# Transceiver.net
KiCad netlist of a schematic drawn in Altium Designer
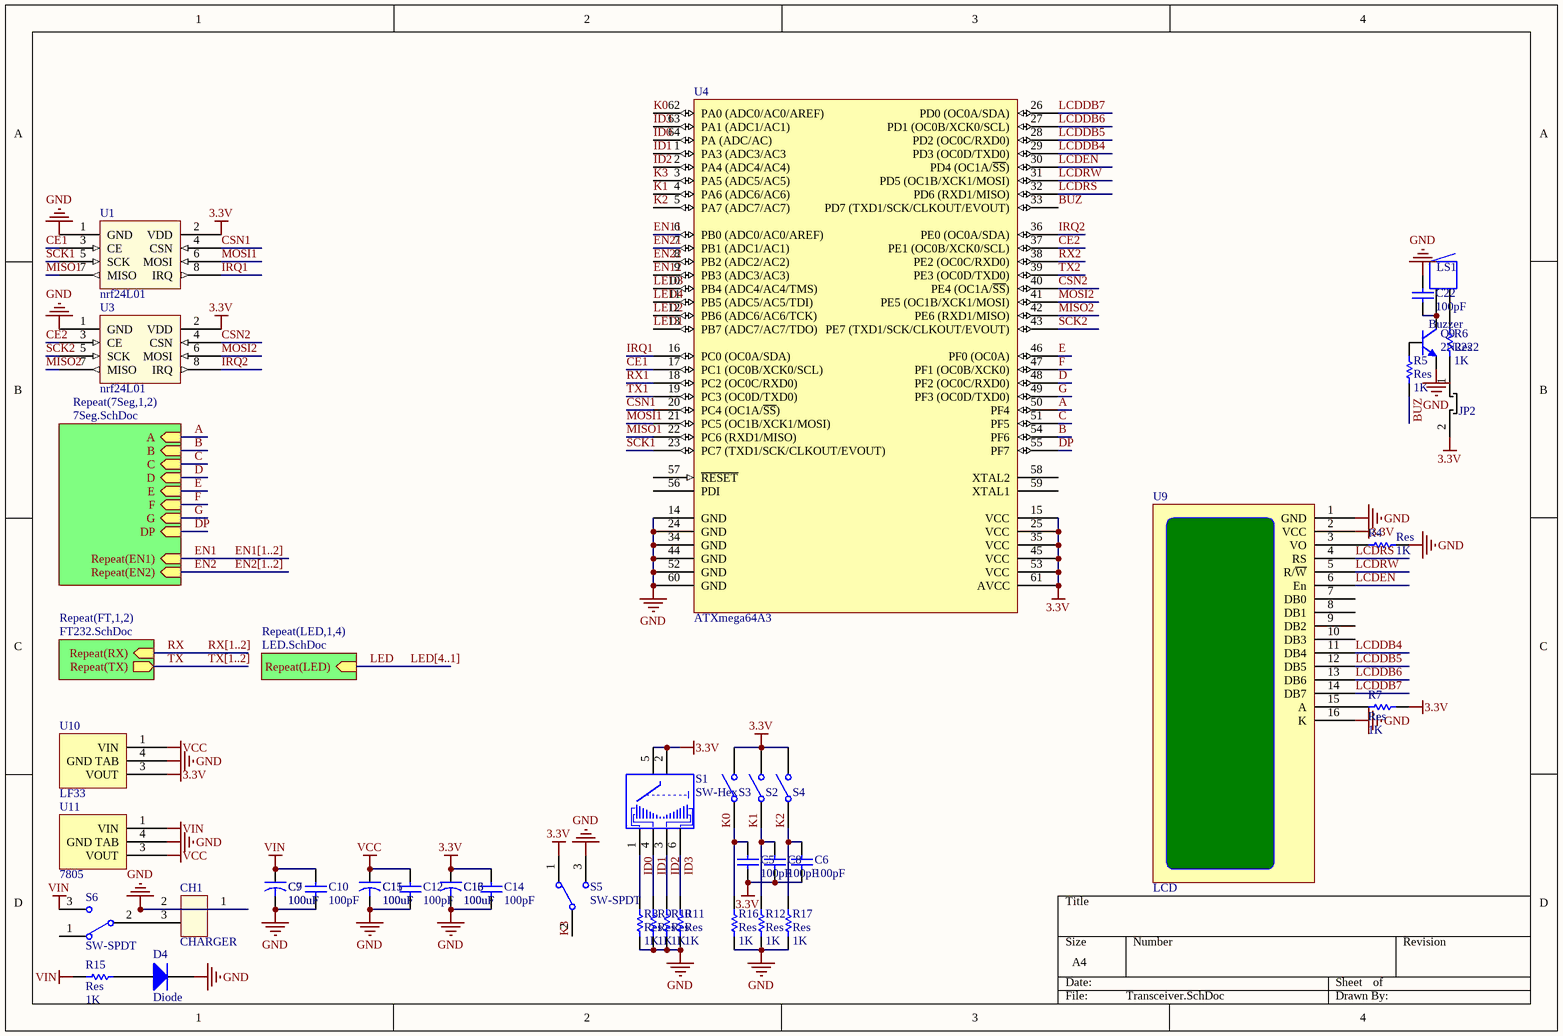
[diagram p0: Transceiver.SchDoc]

(export (version "E")
  (design (tool "Eeschema 10.0.6"))
  (components
    (comp (ref "C5")
      (value "100pF")
      (footprint "2012[0805]")
      (description "Capacitor")
      (fields (field (name "Comment") "Cap_UP") (field (name "PUBLISHER") "Altium Limited"))
      (libsource (lib "KN2CLib") (part "Cap_UP"))
    )
    (comp (ref "C6")
      (value "100pF")
      (footprint "2012[0805]")
      (description "Capacitor")
      (fields (field (name "Comment") "Cap_UP") (field (name "PUBLISHER") "Altium Limited"))
      (libsource (lib "KN2CLib") (part "Cap_UP"))
    )
    (comp (ref "C7")
      (value "100uF")
      (footprint "EL_M")
      (description "Capacitor")
      (fields (field (name "Comment") "Cap_El") (field (name "PUBLISHER") "Altium Limited"))
      (libsource (lib "KN2CLib") (part "Cap_El"))
    )
    (comp (ref "C8")
      (value "100pF")
      (footprint "2012[0805]")
      (description "Capacitor")
      (fields (field (name "Comment") "Cap_UP") (field (name "PUBLISHER") "Altium Limited"))
      (libsource (lib "KN2CLib") (part "Cap_UP"))
    )
    (comp (ref "C9")
      (value "100uF")
      (footprint "EL_M")
      (description "Capacitor")
      (fields (field (name "Comment") "Cap_El") (field (name "PUBLISHER") "Altium Limited"))
      (libsource (lib "KN2CLib") (part "Cap_El"))
    )
    (comp (ref "C10")
      (value "100pF")
      (footprint "2012[0805]")
      (description "Capacitor")
      (fields (field (name "Comment") "Cap_UP") (field (name "PUBLISHER") "Altium Limited"))
      (libsource (lib "KN2CLib") (part "Cap_UP"))
    )
    (comp (ref "C11")
      (value "100uF")
      (footprint "EL_M")
      (description "Capacitor")
      (fields (field (name "Comment") "Cap_El") (field (name "PUBLISHER") "Altium Limited"))
      (libsource (lib "KN2CLib") (part "Cap_El"))
    )
    (comp (ref "C12")
      (value "100pF")
      (footprint "2012[0805]")
      (description "Capacitor")
      (fields (field (name "Comment") "Cap_UP") (field (name "PUBLISHER") "Altium Limited"))
      (libsource (lib "KN2CLib") (part "Cap_UP"))
    )
    (comp (ref "C13")
      (value "100uF")
      (footprint "EL_M")
      (description "Capacitor")
      (fields (field (name "Comment") "Cap_El") (field (name "PUBLISHER") "Altium Limited"))
      (libsource (lib "KN2CLib") (part "Cap_El"))
    )
    (comp (ref "C14")
      (value "100pF")
      (footprint "2012[0805]")
      (description "Capacitor")
      (fields (field (name "Comment") "Cap_UP") (field (name "PUBLISHER") "Altium Limited"))
      (libsource (lib "KN2CLib") (part "Cap_UP"))
    )
    (comp (ref "C15")
      (value "100uF")
      (footprint "EL_M")
      (description "Capacitor")
      (fields (field (name "Comment") "Cap_El") (field (name "PUBLISHER") "Altium Limited"))
      (libsource (lib "KN2CLib") (part "Cap_El"))
    )
    (comp (ref "C16")
      (value "100uF")
      (footprint "EL_M")
      (description "Capacitor")
      (fields (field (name "Comment") "Cap_El") (field (name "PUBLISHER") "Altium Limited"))
      (libsource (lib "KN2CLib") (part "Cap_El"))
    )
    (comp (ref "C22")
      (value "100pF")
      (footprint "2012[0805]")
      (description "Capacitor")
      (fields (field (name "Comment") "Cap_UP") (field (name "PUBLISHER") "Altium Limited"))
      (libsource (lib "KN2CLib") (part "Cap_UP"))
    )
    (comp (ref "CH1") (value "CHARGER") (footprint "CHARGER") (libsource (lib "KN2CLib") (part "CHARGER")))
    (comp (ref "D4")
      (value "Diode")
      (footprint "2012[0805]")
      (description "1 Amp General Purpose Rectifier")
      (fields (field (name "PUBLISHER") "Altium Limited"))
      (libsource (lib "KN2CLib") (part "Diode"))
    )
    (comp (ref "JP2") (value "JUMPER") (footprint "HDR1X2") (libsource (lib "KN2CLib") (part "JUMPER")))
    (comp (ref "LS1")
      (value "Buzzer")
      (footprint "BUZZER")
      (description "Magnetic Transducer Buzzer")
      (fields (field (name "PUBLISHER") "Altium Limited"))
      (libsource (lib "KN2CLib") (part "Buzzer"))
    )
    (comp (ref "Q9")
      (value "2N2222")
      (footprint "SOT-23")
      (description "NPN Bipolar Transistor")
      (fields (field (name "PUBLISHER") "Altium Limited"))
      (libsource (lib "KN2CLib") (part "2N2222"))
    )
    (comp (ref "R4")
      (value "Res")
      (footprint "2012[0805]")
      (description "Semiconductor Resistor")
      (fields (field (name "ALTIUM_VALUE") "1K") (field (name "PUBLISHER") "Altium Limited"))
      (libsource (lib "KN2CLib") (part "Res"))
    )
    (comp (ref "R5")
      (value "Res")
      (footprint "2012[0805]")
      (description "Semiconductor Resistor")
      (fields (field (name "ALTIUM_VALUE") "1K") (field (name "PUBLISHER") "Altium Limited"))
      (libsource (lib "KN2CLib") (part "Res"))
    )
    (comp (ref "R6")
      (value "Res")
      (footprint "2012[0805]")
      (description "Semiconductor Resistor")
      (fields (field (name "ALTIUM_VALUE") "1K") (field (name "PUBLISHER") "Altium Limited"))
      (libsource (lib "KN2CLib") (part "Res"))
    )
    (comp (ref "R7")
      (value "Res")
      (footprint "2012[0805]")
      (description "Semiconductor Resistor")
      (fields (field (name "ALTIUM_VALUE") "1K") (field (name "PUBLISHER") "Altium Limited"))
      (libsource (lib "KN2CLib") (part "Res"))
    )
    (comp (ref "R8")
      (value "Res")
      (footprint "2012[0805]")
      (description "Semiconductor Resistor")
      (fields (field (name "ALTIUM_VALUE") "1K") (field (name "PUBLISHER") "Altium Limited"))
      (libsource (lib "KN2CLib") (part "Res"))
    )
    (comp (ref "R9")
      (value "Res")
      (footprint "2012[0805]")
      (description "Semiconductor Resistor")
      (fields (field (name "ALTIUM_VALUE") "1K") (field (name "PUBLISHER") "Altium Limited"))
      (libsource (lib "KN2CLib") (part "Res"))
    )
    (comp (ref "R10")
      (value "Res")
      (footprint "2012[0805]")
      (description "Semiconductor Resistor")
      (fields (field (name "ALTIUM_VALUE") "1K") (field (name "PUBLISHER") "Altium Limited"))
      (libsource (lib "KN2CLib") (part "Res"))
    )
    (comp (ref "R11")
      (value "Res")
      (footprint "2012[0805]")
      (description "Semiconductor Resistor")
      (fields (field (name "ALTIUM_VALUE") "1K") (field (name "PUBLISHER") "Altium Limited"))
      (libsource (lib "KN2CLib") (part "Res"))
    )
    (comp (ref "R12")
      (value "Res")
      (footprint "2012[0805]")
      (description "Semiconductor Resistor")
      (fields (field (name "ALTIUM_VALUE") "1K") (field (name "PUBLISHER") "Altium Limited"))
      (libsource (lib "KN2CLib") (part "Res"))
    )
    (comp (ref "R15")
      (value "Res")
      (footprint "2012[0805]")
      (description "Semiconductor Resistor")
      (fields (field (name "ALTIUM_VALUE") "1K") (field (name "PUBLISHER") "Altium Limited"))
      (libsource (lib "KN2CLib") (part "Res"))
    )
    (comp (ref "R16")
      (value "Res")
      (footprint "2012[0805]")
      (description "Semiconductor Resistor")
      (fields (field (name "ALTIUM_VALUE") "1K") (field (name "PUBLISHER") "Altium Limited"))
      (libsource (lib "KN2CLib") (part "Res"))
    )
    (comp (ref "R17")
      (value "Res")
      (footprint "2012[0805]")
      (description "Semiconductor Resistor")
      (fields (field (name "ALTIUM_VALUE") "1K") (field (name "PUBLISHER") "Altium Limited"))
      (libsource (lib "KN2CLib") (part "Res"))
    )
    (comp (ref "S1")
      (value "SW-Hex")
      (footprint "SW-HEX")
      (fields (field (name "PUBLISHER") "Altium Limited"))
      (libsource (lib "KN2CLib") (part "SW-Hex"))
    )
    (comp (ref "S2")
      (value "SW-SPST")
      (footprint "PUSH-BUT-SMD")
      (description "Single-Pole, Single-Throw Switch")
      (fields (field (name "PUBLISHER") "Altium Limited"))
      (libsource (lib "KN2CLib") (part "SW-SPST"))
    )
    (comp (ref "S3")
      (value "SW-SPST")
      (footprint "PUSH-BUT")
      (description "Single-Pole, Single-Throw Switch")
      (fields (field (name "PUBLISHER") "Altium Limited"))
      (libsource (lib "KN2CLib") (part "SW-SPST"))
    )
    (comp (ref "S4")
      (value "SW-SPST")
      (footprint "PUSH-BUT")
      (description "Single-Pole, Single-Throw Switch")
      (fields (field (name "PUBLISHER") "Altium Limited"))
      (libsource (lib "KN2CLib") (part "SW-SPST"))
    )
    (comp (ref "S5")
      (value "SW-SPDT")
      (footprint "SW-SPDT")
      (description "SPDT Subminiature Toggle Switch, Right Angle Mounting, Vertical Actuation")
      (fields (field (name "PUBLISHER") "Altium Limited"))
      (libsource (lib "KN2CLib") (part "SW-SPDT"))
    )
    (comp (ref "S6")
      (value "SW-SPDT")
      (footprint "SW-SPDT")
      (description "SPDT Subminiature Toggle Switch, Right Angle Mounting, Vertical Actuation")
      (fields (field (name "PUBLISHER") "Altium Limited"))
      (libsource (lib "KN2CLib") (part "SW-SPDT"))
    )
    (comp (ref "U1")
      (value "nrf24L01")
      (footprint "NRF24L01+PA+LNA")
      (libsource (lib "KN2CLib") (part "nrf24L01"))
    )
    (comp (ref "U3")
      (value "nrf24L01")
      (footprint "NRF24L01+PA+LNA")
      (libsource (lib "KN2CLib") (part "nrf24L01"))
    )
    (comp (ref "U4")
      (value "ATXmega64A3")
      (footprint "64A_N")
      (libsource (lib "KN2CLib") (part "ATXmega64A3"))
    )
    (comp (ref "U9")
      (value "LCD")
      (footprint "LCD")
      (description "LCD 2X16")
      (libsource (lib "KN2CLib") (part "LCD"))
    )
    (comp (ref "U10") (value "LF33") (footprint "D-PACK") (libsource (lib "KN2CLib") (part "7805")))
    (comp (ref "U11") (value "7805") (footprint "D-PACK") (libsource (lib "KN2CLib") (part "7805")))
  )
  (nets
    (net (code "1") (name "/A") (class "Default")
      (node (ref "U4") (pin "50") (pinfunction "PF4_50") (pintype "bidirectional"))
    )
    (net (code "2") (name "/B") (class "Default")
      (node (ref "U4") (pin "54") (pinfunction "PF6_54") (pintype "bidirectional"))
    )
    (net (code "3") (name "/BUZ") (class "Default")
      (node (ref "R5") (pin "2") (pinfunction "2_2") (pintype "passive"))
      (node (ref "U4") (pin "33") (pinfunction "PD7_(TXD1/SCK/CLKOUT/EVOUT)_33") (pintype "bidirectional"))
    )
    (net (code "4") (name "/C") (class "Default")
      (node (ref "U4") (pin "51") (pinfunction "PF5_51") (pintype "bidirectional"))
    )
    (net (code "5") (name "/CE1") (class "Default")
      (node (ref "U1") (pin "3") (pinfunction "CE_3") (pintype "input"))
      (node (ref "U4") (pin "17") (pinfunction "PC1_(OC0B/XCK0/SCL)_17") (pintype "bidirectional"))
    )
    (net (code "6") (name "/CE2") (class "Default")
      (node (ref "U3") (pin "3") (pinfunction "CE_3") (pintype "input"))
      (node (ref "U4") (pin "37") (pinfunction "PE1_(OC0B/XCK0/SCL)_37") (pintype "bidirectional"))
    )
    (net (code "7") (name "/CSN1") (class "Default")
      (node (ref "U1") (pin "4") (pinfunction "CSN_4") (pintype "input"))
      (node (ref "U4") (pin "20") (pinfunction "PC4_(OC1A/~{SS})_20") (pintype "bidirectional"))
    )
    (net (code "8") (name "/CSN2") (class "Default")
      (node (ref "U3") (pin "4") (pinfunction "CSN_4") (pintype "input"))
      (node (ref "U4") (pin "40") (pinfunction "PE4_(OC1A/~{SS})_40") (pintype "bidirectional"))
    )
    (net (code "9") (name "/D") (class "Default")
      (node (ref "U4") (pin "48") (pinfunction "PF2_(OC0C/RXD0)_48") (pintype "bidirectional"))
    )
    (net (code "10") (name "/DP") (class "Default")
      (node (ref "U4") (pin "55") (pinfunction "PF7_55") (pintype "bidirectional"))
    )
    (net (code "11") (name "/E") (class "Default")
      (node (ref "U4") (pin "46") (pinfunction "PF0_(OC0A)_46") (pintype "bidirectional"))
    )
    (net (code "16") (name "/EN11") (class "Default")
      (node (ref "U4") (pin "6") (pinfunction "PB0_(ADC0/AC0/AREF)_6") (pintype "bidirectional"))
    )
    (net (code "17") (name "/EN12") (class "Default")
      (node (ref "U4") (pin "9") (pinfunction "PB3_(ADC3/AC3)_9") (pintype "bidirectional"))
    )
    (net (code "18") (name "/EN21") (class "Default")
      (node (ref "U4") (pin "7") (pinfunction "PB1_(ADC1/AC1)_7") (pintype "bidirectional"))
    )
    (net (code "19") (name "/EN22") (class "Default")
      (node (ref "U4") (pin "8") (pinfunction "PB2_(ADC2/AC2)_8") (pintype "bidirectional"))
    )
    (net (code "20") (name "/F") (class "Default")
      (node (ref "U4") (pin "47") (pinfunction "PF1_(OC0B/XCK0)_47") (pintype "bidirectional"))
    )
    (net (code "21") (name "/G") (class "Default")
      (node (ref "U4") (pin "49") (pinfunction "PF3_(OC0D/TXD0)_49") (pintype "bidirectional"))
    )
    (net (code "22") (name "/ID0") (class "Default")
      (node (ref "R8") (pin "2") (pinfunction "2_2") (pintype "passive"))
      (node (ref "S1") (pin "1") (pinfunction "1_1") (pintype "passive"))
      (node (ref "U4") (pin "64") (pinfunction "PA_(ADC/AC)_64") (pintype "bidirectional"))
    )
    (net (code "23") (name "/ID1") (class "Default")
      (node (ref "R9") (pin "2") (pinfunction "2_2") (pintype "passive"))
      (node (ref "S1") (pin "4") (pinfunction "4_4") (pintype "passive"))
      (node (ref "U4") (pin "1") (pinfunction "PA3_(ADC3/AC3_1") (pintype "bidirectional"))
    )
    (net (code "24") (name "/ID2") (class "Default")
      (node (ref "R10") (pin "2") (pinfunction "2_2") (pintype "passive"))
      (node (ref "S1") (pin "3") (pinfunction "3_3") (pintype "passive"))
      (node (ref "U4") (pin "2") (pinfunction "PA4_(ADC4/AC4)_2") (pintype "bidirectional"))
    )
    (net (code "25") (name "/ID3") (class "Default")
      (node (ref "R11") (pin "2") (pinfunction "2_2") (pintype "passive"))
      (node (ref "S1") (pin "6") (pinfunction "6_6") (pintype "passive"))
      (node (ref "U4") (pin "63") (pinfunction "PA1_(ADC1/AC1)_63") (pintype "bidirectional"))
    )
    (net (code "26") (name "/IRQ1") (class "Default")
      (node (ref "U1") (pin "8") (pinfunction "IRQ_8") (pintype "output"))
      (node (ref "U4") (pin "16") (pinfunction "PC0_(OC0A/SDA)_16") (pintype "bidirectional"))
    )
    (net (code "27") (name "/IRQ2") (class "Default")
      (node (ref "U3") (pin "8") (pinfunction "IRQ_8") (pintype "output"))
      (node (ref "U4") (pin "36") (pinfunction "PE0_(OC0A/SDA)_36") (pintype "bidirectional"))
    )
    (net (code "28") (name "/K0") (class "Default")
      (node (ref "C5") (pin "1") (pinfunction "1_1") (pintype "passive"))
      (node (ref "R16") (pin "2") (pinfunction "2_2") (pintype "passive"))
      (node (ref "S3") (pin "1") (pinfunction "COMMON_1") (pintype "passive"))
      (node (ref "U4") (pin "62") (pinfunction "PA0_(ADC0/AC0/AREF)_62") (pintype "bidirectional"))
    )
    (net (code "29") (name "/K1") (class "Default")
      (node (ref "C8") (pin "1") (pinfunction "1_1") (pintype "passive"))
      (node (ref "R12") (pin "2") (pinfunction "2_2") (pintype "passive"))
      (node (ref "S2") (pin "1") (pinfunction "COMMON_1") (pintype "passive"))
      (node (ref "U4") (pin "4") (pinfunction "PA6_(ADC6/AC6)_4") (pintype "bidirectional"))
    )
    (net (code "30") (name "/K2") (class "Default")
      (node (ref "C6") (pin "1") (pinfunction "1_1") (pintype "passive"))
      (node (ref "R17") (pin "2") (pinfunction "2_2") (pintype "passive"))
      (node (ref "S4") (pin "1") (pinfunction "COMMON_1") (pintype "passive"))
      (node (ref "U4") (pin "5") (pinfunction "PA7_(ADC7/AC7)_5") (pintype "bidirectional"))
    )
    (net (code "31") (name "/K3") (class "Default")
      (node (ref "S5") (pin "2") (pinfunction "2_2") (pintype "passive"))
      (node (ref "U4") (pin "3") (pinfunction "PA5_(ADC5/AC5)_3") (pintype "bidirectional"))
    )
    (net (code "32") (name "/LCDDB4") (class "Default")
      (node (ref "U4") (pin "29") (pinfunction "PD3_(OC0D/TXD0)_29") (pintype "bidirectional"))
      (node (ref "U9") (pin "11") (pinfunction "DB4_11") (pintype "passive"))
    )
    (net (code "33") (name "/LCDDB5") (class "Default")
      (node (ref "U4") (pin "28") (pinfunction "PD2_(OC0C/RXD0)_28") (pintype "bidirectional"))
      (node (ref "U9") (pin "12") (pinfunction "DB5_12") (pintype "passive"))
    )
    (net (code "34") (name "/LCDDB6") (class "Default")
      (node (ref "U4") (pin "27") (pinfunction "PD1_(OC0B/XCK0/SCL)_27") (pintype "bidirectional"))
      (node (ref "U9") (pin "13") (pinfunction "DB6_13") (pintype "passive"))
    )
    (net (code "35") (name "/LCDDB7") (class "Default")
      (node (ref "U4") (pin "26") (pinfunction "PD0_(OC0A/SDA)_26") (pintype "bidirectional"))
      (node (ref "U9") (pin "14") (pinfunction "DB7_14") (pintype "passive"))
    )
    (net (code "36") (name "/LCDEN") (class "Default")
      (node (ref "U4") (pin "30") (pinfunction "PD4_(OC1A/~{SS})_30") (pintype "bidirectional"))
      (node (ref "U9") (pin "6") (pinfunction "En_6") (pintype "passive"))
    )
    (net (code "37") (name "/LCDRS") (class "Default")
      (node (ref "U4") (pin "32") (pinfunction "PD6_(RXD1/MISO)_32") (pintype "bidirectional"))
      (node (ref "U9") (pin "4") (pinfunction "RS_4") (pintype "passive"))
    )
    (net (code "38") (name "/LCDRW") (class "Default")
      (node (ref "U4") (pin "31") (pinfunction "PD5_(OC1B/XCK1/MOSI)_31") (pintype "bidirectional"))
      (node (ref "U9") (pin "5") (pinfunction "R/~{W}_5") (pintype "passive"))
    )
    (net (code "40") (name "/LED1") (class "Default")
      (node (ref "U4") (pin "13") (pinfunction "PB7_(ADC7/AC7/TDO)_13") (pintype "bidirectional"))
    )
    (net (code "41") (name "/LED2") (class "Default")
      (node (ref "U4") (pin "12") (pinfunction "PB6_(ADC6/AC6/TCK)_12") (pintype "bidirectional"))
    )
    (net (code "42") (name "/LED3") (class "Default")
      (node (ref "U4") (pin "10") (pinfunction "PB4_(ADC4/AC4/TMS)_10") (pintype "bidirectional"))
    )
    (net (code "43") (name "/LED4") (class "Default")
      (node (ref "U4") (pin "11") (pinfunction "PB5_(ADC5/AC5/TDI)_11") (pintype "bidirectional"))
    )
    (net (code "45") (name "/MISO1") (class "Default")
      (node (ref "U1") (pin "7") (pinfunction "MISO_7") (pintype "output"))
      (node (ref "U4") (pin "22") (pinfunction "PC6_(RXD1/MISO)_22") (pintype "bidirectional"))
    )
    (net (code "46") (name "/MISO2") (class "Default")
      (node (ref "U3") (pin "7") (pinfunction "MISO_7") (pintype "output"))
      (node (ref "U4") (pin "42") (pinfunction "PE6_(RXD1/MISO)_42") (pintype "bidirectional"))
    )
    (net (code "47") (name "/MOSI1") (class "Default")
      (node (ref "U1") (pin "6") (pinfunction "MOSI_6") (pintype "input"))
      (node (ref "U4") (pin "21") (pinfunction "PC5_(OC1B/XCK1/MOSI)_21") (pintype "bidirectional"))
    )
    (net (code "48") (name "/MOSI2") (class "Default")
      (node (ref "U3") (pin "6") (pinfunction "MOSI_6") (pintype "input"))
      (node (ref "U4") (pin "41") (pinfunction "PE5_(OC1B/XCK1/MOSI)_41") (pintype "bidirectional"))
    )
    (net (code "50") (name "/RX1") (class "Default")
      (node (ref "U4") (pin "18") (pinfunction "PC2_(OC0C/RXD0)_18") (pintype "bidirectional"))
    )
    (net (code "51") (name "/RX2") (class "Default")
      (node (ref "U4") (pin "38") (pinfunction "PE2_(OC0C/RXD0)_38") (pintype "bidirectional"))
    )
    (net (code "53") (name "/SCK1") (class "Default")
      (node (ref "U1") (pin "5") (pinfunction "SCK_5") (pintype "input"))
      (node (ref "U4") (pin "23") (pinfunction "PC7_(TXD1/SCK/CLKOUT/EVOUT)_23") (pintype "bidirectional"))
    )
    (net (code "54") (name "/SCK2") (class "Default")
      (node (ref "U3") (pin "5") (pinfunction "SCK_5") (pintype "input"))
      (node (ref "U4") (pin "43") (pinfunction "PE7_(TXD1/SCK/CLKOUT/EVOUT)_43") (pintype "bidirectional"))
    )
    (net (code "56") (name "/TX1") (class "Default")
      (node (ref "U4") (pin "19") (pinfunction "PC3_(OC0D/TXD0)_19") (pintype "bidirectional"))
    )
    (net (code "57") (name "/TX2") (class "Default")
      (node (ref "U4") (pin "39") (pinfunction "PE3_(OC0D/TXD0)_39") (pintype "bidirectional"))
    )
    (net (code "59") (name "3.3V") (class "Default")
      (node (ref "C13") (pin "1") (pinfunction "1_1") (pintype "passive"))
      (node (ref "C14") (pin "2") (pinfunction "2_2") (pintype "passive"))
      (node (ref "C16") (pin "1") (pinfunction "1_1") (pintype "passive"))
      (node (ref "C5") (pin "2") (pinfunction "2_2") (pintype "passive"))
      (node (ref "C6") (pin "2") (pinfunction "2_2") (pintype "passive"))
      (node (ref "C8") (pin "2") (pinfunction "2_2") (pintype "passive"))
      (node (ref "JP2") (pin "2") (pinfunction "2_2") (pintype "passive"))
      (node (ref "R7") (pin "2") (pinfunction "2_2") (pintype "passive"))
      (node (ref "S1") (pin "2") (pinfunction "2_2") (pintype "passive"))
      (node (ref "S1") (pin "5") (pinfunction "5_5") (pintype "passive"))
      (node (ref "S2") (pin "2") (pinfunction "NO_2") (pintype "passive"))
      (node (ref "S3") (pin "2") (pinfunction "NO_2") (pintype "passive"))
      (node (ref "S4") (pin "2") (pinfunction "NO_2") (pintype "passive"))
      (node (ref "S5") (pin "1") (pinfunction "3_1") (pintype "passive"))
      (node (ref "U1") (pin "2") (pinfunction "VDD_2") (pintype "power_in"))
      (node (ref "U10") (pin "3") (pinfunction "VOUT_3") (pintype "passive"))
      (node (ref "U3") (pin "2") (pinfunction "VDD_2") (pintype "power_in"))
      (node (ref "U4") (pin "15") (pinfunction "VCC_15") (pintype "power_in"))
      (node (ref "U4") (pin "25") (pinfunction "VCC_25") (pintype "power_in"))
      (node (ref "U4") (pin "35") (pinfunction "VCC_35") (pintype "power_in"))
      (node (ref "U4") (pin "45") (pinfunction "VCC_45") (pintype "power_in"))
      (node (ref "U4") (pin "53") (pinfunction "VCC_53") (pintype "power_in"))
      (node (ref "U4") (pin "61") (pinfunction "AVCC_61") (pintype "power_in"))
      (node (ref "U9") (pin "2") (pinfunction "VCC_2") (pintype "passive"))
    )
    (net (code "60") (name "GND") (class "Default")
      (node (ref "C10") (pin "1") (pinfunction "1_1") (pintype "passive"))
      (node (ref "C11") (pin "2") (pinfunction "2_2") (pintype "passive"))
      (node (ref "C12") (pin "1") (pinfunction "1_1") (pintype "passive"))
      (node (ref "C13") (pin "2") (pinfunction "2_2") (pintype "passive"))
      (node (ref "C14") (pin "1") (pinfunction "1_1") (pintype "passive"))
      (node (ref "C15") (pin "2") (pinfunction "2_2") (pintype "passive"))
      (node (ref "C16") (pin "2") (pinfunction "2_2") (pintype "passive"))
      (node (ref "C22") (pin "2") (pinfunction "2_2") (pintype "passive"))
      (node (ref "C7") (pin "2") (pinfunction "2_2") (pintype "passive"))
      (node (ref "C9") (pin "2") (pinfunction "2_2") (pintype "passive"))
      (node (ref "CH1") (pin "1") (pinfunction "1_1") (pintype "passive"))
      (node (ref "CH1") (pin "2") (pinfunction "2_2") (pintype "passive"))
      (node (ref "D4") (pin "2") (pinfunction "K_2") (pintype "passive"))
      (node (ref "Q9") (pin "3") (pinfunction "E_3") (pintype "passive"))
      (node (ref "R10") (pin "1") (pinfunction "1_1") (pintype "passive"))
      (node (ref "R11") (pin "1") (pinfunction "1_1") (pintype "passive"))
      (node (ref "R12") (pin "1") (pinfunction "1_1") (pintype "passive"))
      (node (ref "R16") (pin "1") (pinfunction "1_1") (pintype "passive"))
      (node (ref "R17") (pin "1") (pinfunction "1_1") (pintype "passive"))
      (node (ref "R4") (pin "2") (pinfunction "2_2") (pintype "passive"))
      (node (ref "R8") (pin "1") (pinfunction "1_1") (pintype "passive"))
      (node (ref "R9") (pin "1") (pinfunction "1_1") (pintype "passive"))
      (node (ref "S5") (pin "3") (pinfunction "1_3") (pintype "passive"))
      (node (ref "U1") (pin "1") (pinfunction "GND_1") (pintype "power_in"))
      (node (ref "U10") (pin "4") (pinfunction "GND_TAB_4") (pintype "passive"))
      (node (ref "U11") (pin "4") (pinfunction "GND_TAB_4") (pintype "passive"))
      (node (ref "U3") (pin "1") (pinfunction "GND_1") (pintype "power_in"))
      (node (ref "U4") (pin "14") (pinfunction "GND_14") (pintype "power_in"))
      (node (ref "U4") (pin "24") (pinfunction "GND_24") (pintype "power_in"))
      (node (ref "U4") (pin "34") (pinfunction "GND_34") (pintype "power_in"))
      (node (ref "U4") (pin "44") (pinfunction "GND_44") (pintype "power_in"))
      (node (ref "U4") (pin "52") (pinfunction "GND_52") (pintype "power_in"))
      (node (ref "U4") (pin "60") (pinfunction "GND_60") (pintype "power_in"))
      (node (ref "U9") (pin "1") (pinfunction "GND_1") (pintype "passive"))
      (node (ref "U9") (pin "16") (pinfunction "K_16") (pintype "passive"))
    )
    (net (code "61") (name "Net-(CH1-Pad3)") (class "Default")
      (node (ref "CH1") (pin "3") (pinfunction "3_3") (pintype "passive"))
      (node (ref "S6") (pin "2") (pinfunction "2_2") (pintype "passive"))
    )
    (net (code "62") (name "Net-(D4-A)") (class "Default")
      (node (ref "D4") (pin "1") (pinfunction "A_1") (pintype "passive"))
      (node (ref "R15") (pin "2") (pinfunction "2_2") (pintype "passive"))
    )
    (net (code "63") (name "Net-(JP2-Pad1)") (class "Default")
      (node (ref "JP2") (pin "1") (pinfunction "1_1") (pintype "passive"))
      (node (ref "R6") (pin "2") (pinfunction "2_2") (pintype "passive"))
    )
    (net (code "64") (name "Net-(LS1-Pad2)") (class "Default")
      (node (ref "LS1") (pin "2") (pinfunction "2_2") (pintype "passive"))
      (node (ref "R6") (pin "1") (pinfunction "1_1") (pintype "passive"))
    )
    (net (code "65") (name "Net-(Q9-B)") (class "Default")
      (node (ref "Q9") (pin "2") (pinfunction "B_2") (pintype "passive"))
      (node (ref "R5") (pin "1") (pinfunction "1_1") (pintype "passive"))
    )
    (net (code "66") (name "Net-(Q9-C)") (class "Default")
      (node (ref "C22") (pin "1") (pinfunction "1_1") (pintype "passive"))
      (node (ref "LS1") (pin "1") (pinfunction "1_1") (pintype "passive"))
      (node (ref "Q9") (pin "1") (pinfunction "C_1") (pintype "passive"))
    )
    (net (code "67") (name "Net-(U9-A)") (class "Default")
      (node (ref "R7") (pin "1") (pinfunction "1_1") (pintype "passive"))
      (node (ref "U9") (pin "15") (pinfunction "A_15") (pintype "passive"))
    )
    (net (code "68") (name "Net-(U9-VO)") (class "Default")
      (node (ref "R4") (pin "1") (pinfunction "1_1") (pintype "passive"))
      (node (ref "U9") (pin "3") (pinfunction "VO_3") (pintype "passive"))
    )
    (net (code "69") (name "VCC") (class "Default")
      (node (ref "C11") (pin "1") (pinfunction "1_1") (pintype "passive"))
      (node (ref "C12") (pin "2") (pinfunction "2_2") (pintype "passive"))
      (node (ref "C15") (pin "1") (pinfunction "1_1") (pintype "passive"))
      (node (ref "U10") (pin "1") (pinfunction "VIN_1") (pintype "passive"))
      (node (ref "U11") (pin "3") (pinfunction "VOUT_3") (pintype "passive"))
    )
    (net (code "70") (name "VIN") (class "Default")
      (node (ref "C10") (pin "2") (pinfunction "2_2") (pintype "passive"))
      (node (ref "C7") (pin "1") (pinfunction "1_1") (pintype "passive"))
      (node (ref "C9") (pin "1") (pinfunction "1_1") (pintype "passive"))
      (node (ref "R15") (pin "1") (pinfunction "1_1") (pintype "passive"))
      (node (ref "S6") (pin "3") (pinfunction "1_3") (pintype "passive"))
      (node (ref "U11") (pin "1") (pinfunction "VIN_1") (pintype "passive"))
    )
    (net (code "71") (name "unconnected-(S6-3-Pad1)") (class "Default")
      (node (ref "S6") (pin "1") (pinfunction "3_1") (pintype "passive"))
    )
    (net (code "72") (name "unconnected-(U4-PDI-Pad56)") (class "Default")
      (node (ref "U4") (pin "56") (pinfunction "PDI_56") (pintype "passive"))
    )
    (net (code "73") (name "unconnected-(U4-XTAL1-Pad59)") (class "Default")
      (node (ref "U4") (pin "59") (pinfunction "XTAL1_59") (pintype "passive"))
    )
    (net (code "74") (name "unconnected-(U4-XTAL2-Pad58)") (class "Default")
      (node (ref "U4") (pin "58") (pinfunction "XTAL2_58") (pintype "passive"))
    )
    (net (code "75") (name "unconnected-(U4-~{RESET}-Pad57)") (class "Default")
      (node (ref "U4") (pin "57") (pinfunction "~{RESET}_57") (pintype "input"))
    )
    (net (code "76") (name "unconnected-(U9-DB0-Pad7)") (class "Default")
      (node (ref "U9") (pin "7") (pinfunction "DB0_7") (pintype "passive"))
    )
    (net (code "77") (name "unconnected-(U9-DB1-Pad8)") (class "Default")
      (node (ref "U9") (pin "8") (pinfunction "DB1_8") (pintype "passive"))
    )
    (net (code "78") (name "unconnected-(U9-DB2-Pad9)") (class "Default")
      (node (ref "U9") (pin "9") (pinfunction "DB2_9") (pintype "passive"))
    )
    (net (code "79") (name "unconnected-(U9-DB3-Pad10)") (class "Default")
      (node (ref "U9") (pin "10") (pinfunction "DB3_10") (pintype "passive"))
    )
  )
)
